# SCH_transmitter.net
KiCad netlist of a schematic drawn in EasyEDA
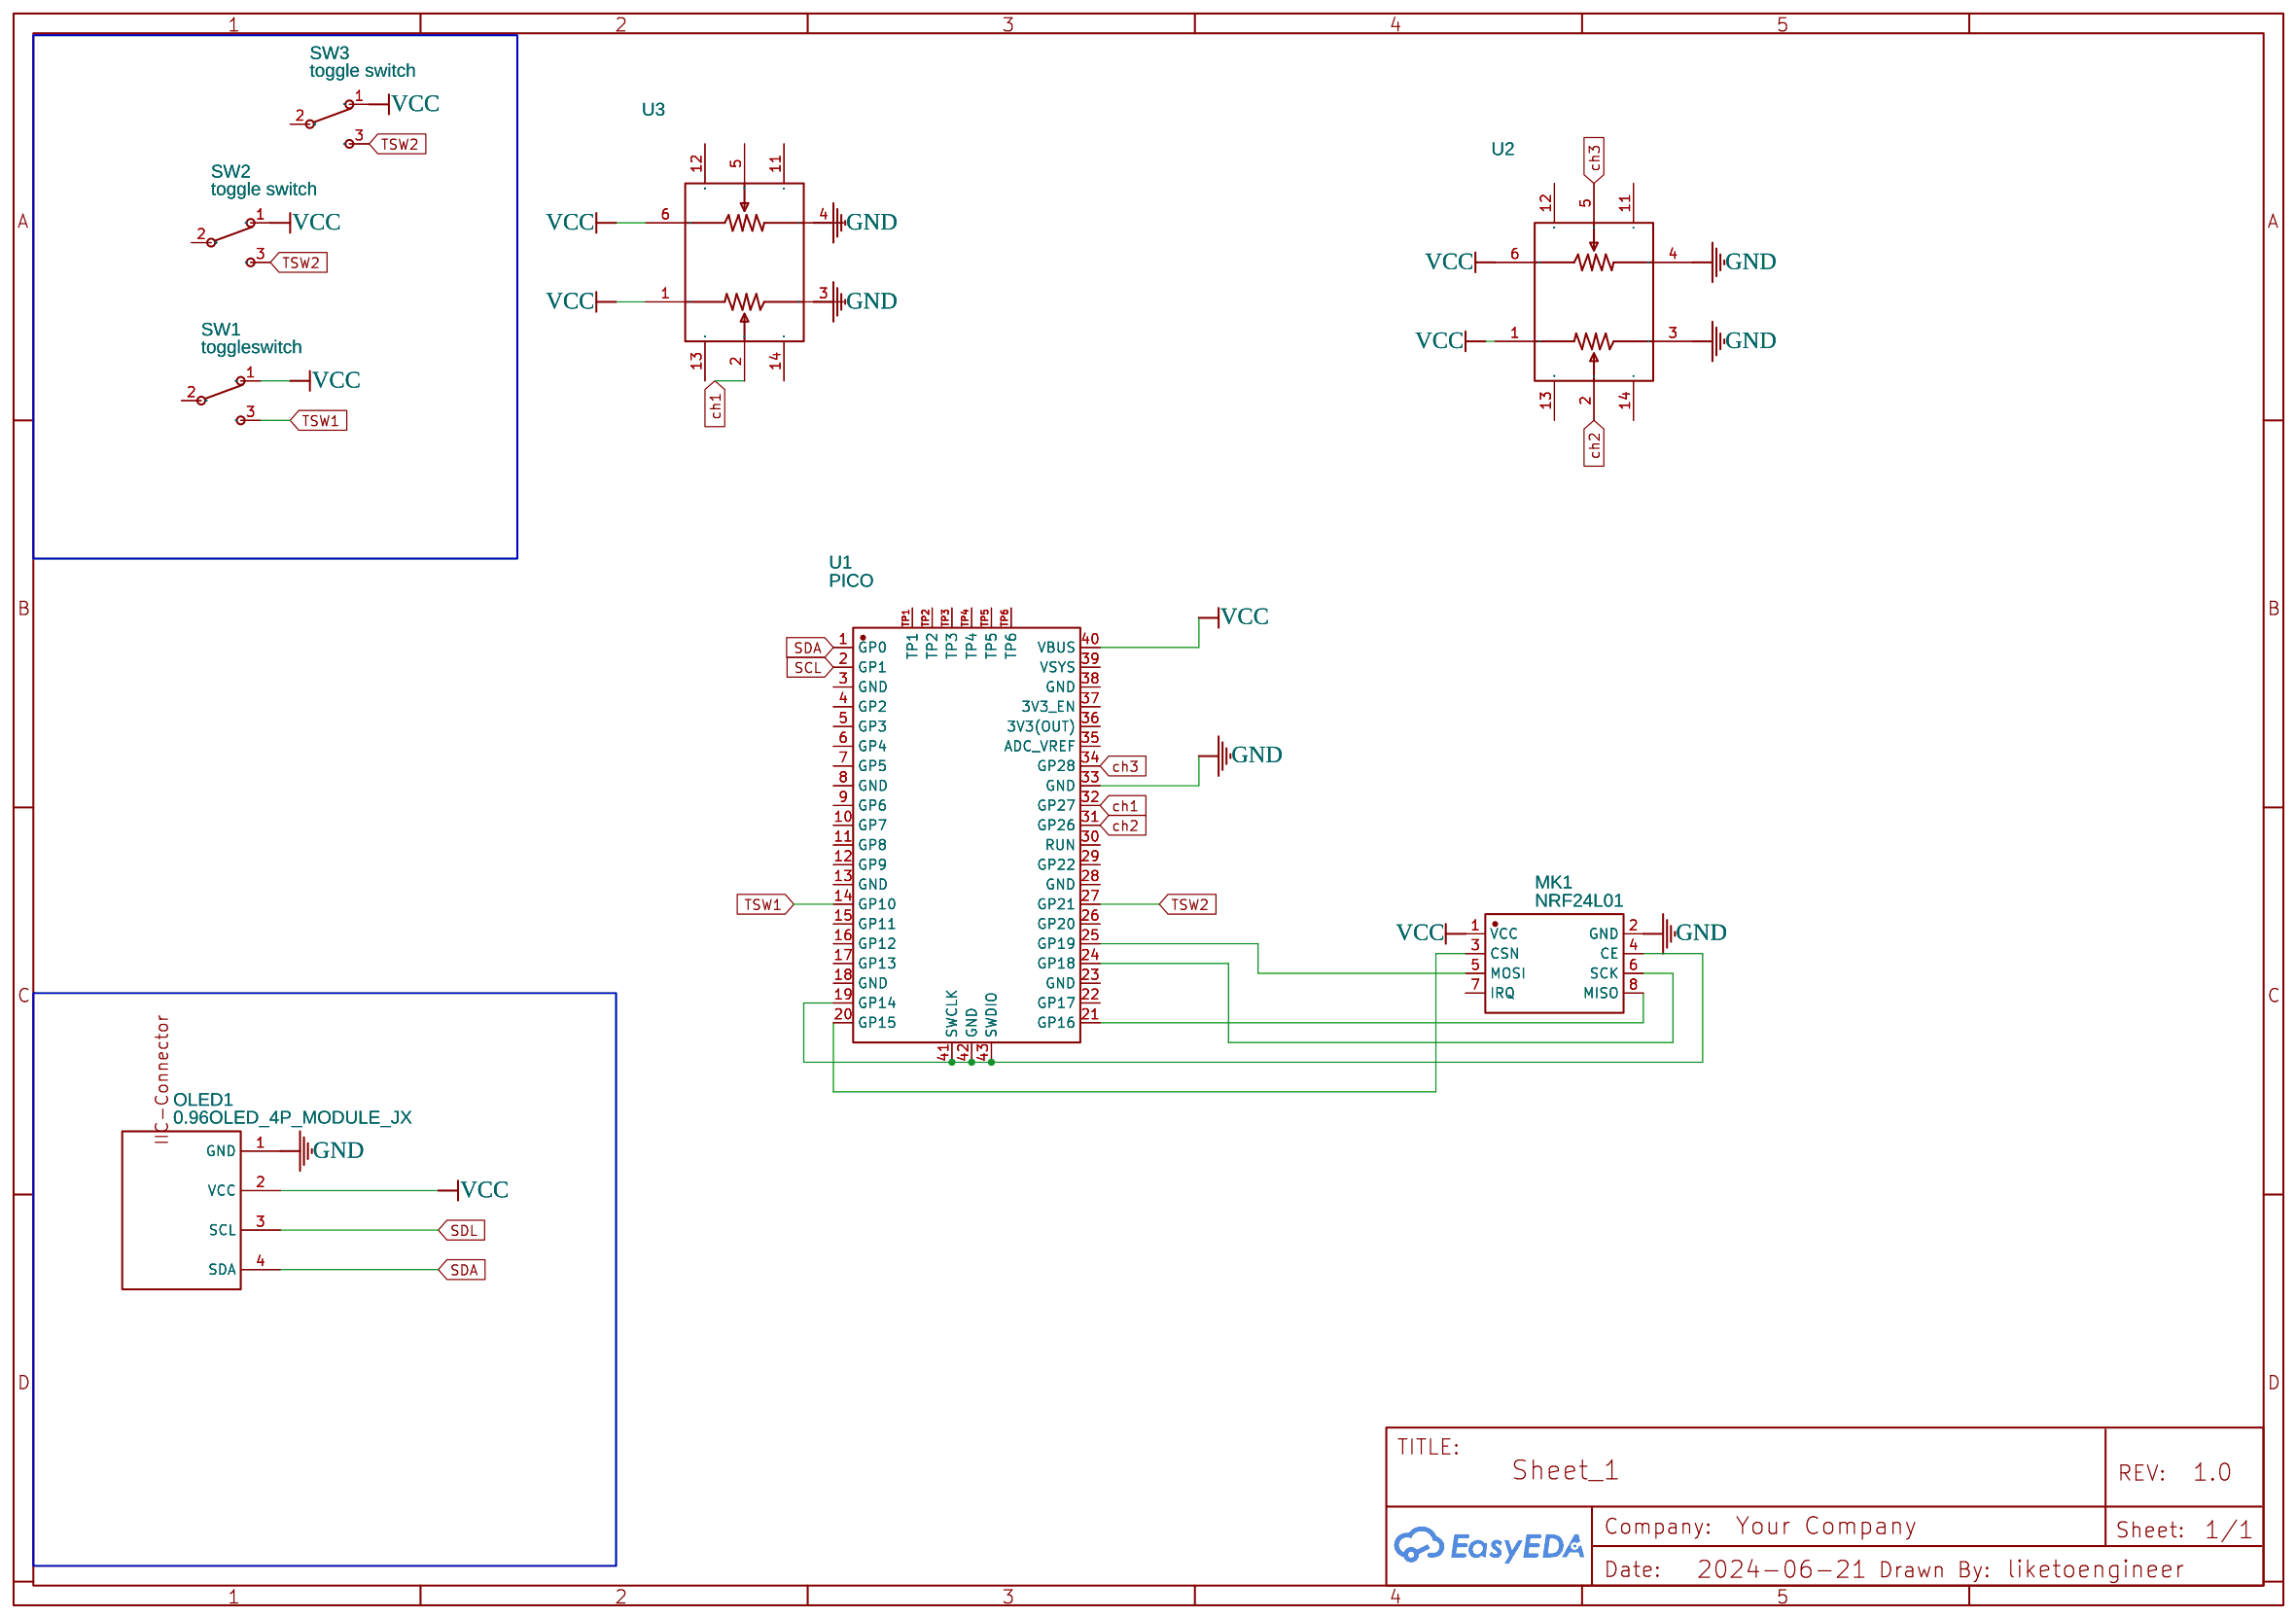
[diagram p0: schematic sheet]

(export (version "E")
  (design (tool "Eeschema 10.0.6"))
  (components
    (comp (ref "MK1")
      (value "NRF24L01")
      (fields (field (name "Manufacturer Part") "NF-04") (field (name "Manufacturer") "Ai-Thinker(安信可)"))
      (libsource (lib "") (part "NRF24L01"))
    )
    (comp (ref "OLED1") (value "0.96OLED_4P_MODULE_JX") (libsource (lib "") (part "0.96OLED_4P_MODULE_JX")))
    (comp (ref "SW1")
      (value "toggleswitch")
      (fields (field (name "Manufacturer Part") "100SP1T2B4M6QE"))
      (libsource (lib "") (part "100SP1T2B4M6QE"))
    )
    (comp (ref "SW2")
      (value "toggle switch")
      (fields (field (name "Manufacturer Part") "100SP1T2B4M6QE"))
      (libsource (lib "") (part "100SP1T2B4M6QE"))
    )
    (comp (ref "SW3")
      (value "toggle switch")
      (fields (field (name "Manufacturer Part") "100SP1T2B4M6QE"))
      (libsource (lib "") (part "100SP1T2B4M6QE"))
    )
    (comp (ref "U1")
      (value "PICO")
      (fields (field (name "Manufacturer") "Raspberry Pi(树莓派)"))
      (libsource (lib "") (part "PICO"))
    )
    (comp (ref "U2")
      (value "252A103B60NA")
      (fields (field (name "Manufacturer") "CTS(西迪斯)"))
      (libsource (lib "") (part "252A103B60NA"))
    )
    (comp (ref "U3")
      (value "252A103B60NA")
      (fields (field (name "Manufacturer") "CTS(西迪斯)"))
      (libsource (lib "") (part "252A103B60NA"))
    )
  )
  (nets
    (net (code "1") (name "GND") (class "Default")
      (node (ref "MK1") (pin "2") (pinfunction "GND_2") (pintype "unspecified"))
      (node (ref "OLED1") (pin "1") (pinfunction "GND_1") (pintype "unspecified"))
      (node (ref "U1") (pin "33") (pinfunction "GND_33") (pintype "unspecified"))
      (node (ref "U2") (pin "3") (pinfunction "3_3") (pintype "unspecified"))
      (node (ref "U2") (pin "4") (pinfunction "4_4") (pintype "unspecified"))
      (node (ref "U3") (pin "3") (pinfunction "3_3") (pintype "unspecified"))
      (node (ref "U3") (pin "4") (pinfunction "4_4") (pintype "unspecified"))
    )
    (net (code "2") (name "Net-(MK1-CE)") (class "Default")
      (node (ref "MK1") (pin "4") (pinfunction "CE_4") (pintype "unspecified"))
      (node (ref "U1") (pin "19") (pinfunction "GP14_19") (pintype "unspecified"))
      (node (ref "U1") (pin "41") (pinfunction "SWCLK_41") (pintype "unspecified"))
      (node (ref "U1") (pin "42") (pinfunction "GND_42") (pintype "unspecified"))
      (node (ref "U1") (pin "43") (pinfunction "SWDIO_43") (pintype "unspecified"))
    )
    (net (code "3") (name "Net-(MK1-CSN)") (class "Default")
      (node (ref "MK1") (pin "3") (pinfunction "CSN_3") (pintype "unspecified"))
      (node (ref "U1") (pin "20") (pinfunction "GP15_20") (pintype "unspecified"))
    )
    (net (code "4") (name "Net-(MK1-MISO)") (class "Default")
      (node (ref "MK1") (pin "8") (pinfunction "MISO_8") (pintype "unspecified"))
      (node (ref "U1") (pin "21") (pinfunction "GP16_21") (pintype "unspecified"))
    )
    (net (code "5") (name "Net-(MK1-MOSI)") (class "Default")
      (node (ref "MK1") (pin "5") (pinfunction "MOSI_5") (pintype "unspecified"))
      (node (ref "U1") (pin "25") (pinfunction "GP19_25") (pintype "unspecified"))
    )
    (net (code "6") (name "Net-(MK1-SCK)") (class "Default")
      (node (ref "MK1") (pin "6") (pinfunction "SCK_6") (pintype "unspecified"))
      (node (ref "U1") (pin "24") (pinfunction "GP18_24") (pintype "unspecified"))
    )
    (net (code "7") (name "SCL") (class "Default")
      (node (ref "U1") (pin "2") (pinfunction "GP1_2") (pintype "unspecified"))
    )
    (net (code "8") (name "SDA") (class "Default")
      (node (ref "OLED1") (pin "4") (pinfunction "SDA_4") (pintype "unspecified"))
      (node (ref "U1") (pin "1") (pinfunction "GP0_1") (pintype "unspecified"))
    )
    (net (code "9") (name "SDL") (class "Default")
      (node (ref "OLED1") (pin "3") (pinfunction "SCL_3") (pintype "unspecified"))
    )
    (net (code "10") (name "TSW1") (class "Default")
      (node (ref "SW1") (pin "3") (pinfunction "NC_3") (pintype "unspecified"))
      (node (ref "U1") (pin "14") (pinfunction "GP10_14") (pintype "unspecified"))
    )
    (net (code "11") (name "TSW2") (class "Default")
      (node (ref "SW2") (pin "3") (pinfunction "NC_3") (pintype "unspecified"))
      (node (ref "SW3") (pin "3") (pinfunction "NC_3") (pintype "unspecified"))
      (node (ref "U1") (pin "27") (pinfunction "GP21_27") (pintype "unspecified"))
    )
    (net (code "12") (name "VCC") (class "Default")
      (node (ref "MK1") (pin "1") (pinfunction "VCC_1") (pintype "unspecified"))
      (node (ref "OLED1") (pin "2") (pinfunction "VCC_2") (pintype "unspecified"))
      (node (ref "SW1") (pin "1") (pinfunction "ON_1") (pintype "unspecified"))
      (node (ref "SW2") (pin "1") (pinfunction "ON_1") (pintype "unspecified"))
      (node (ref "SW3") (pin "1") (pinfunction "ON_1") (pintype "unspecified"))
      (node (ref "U1") (pin "40") (pinfunction "VBUS_40") (pintype "unspecified"))
      (node (ref "U2") (pin "1") (pinfunction "1_1") (pintype "unspecified"))
      (node (ref "U2") (pin "6") (pinfunction "6_6") (pintype "unspecified"))
      (node (ref "U3") (pin "1") (pinfunction "1_1") (pintype "unspecified"))
      (node (ref "U3") (pin "6") (pinfunction "6_6") (pintype "unspecified"))
    )
    (net (code "13") (name "ch1") (class "Default")
      (node (ref "U1") (pin "32") (pinfunction "GP27_32") (pintype "unspecified"))
      (node (ref "U3") (pin "2") (pinfunction "2_2") (pintype "unspecified"))
    )
    (net (code "14") (name "ch2") (class "Default")
      (node (ref "U1") (pin "31") (pinfunction "GP26_31") (pintype "unspecified"))
      (node (ref "U2") (pin "2") (pinfunction "2_2") (pintype "unspecified"))
    )
    (net (code "15") (name "ch3") (class "Default")
      (node (ref "U1") (pin "34") (pinfunction "GP28_34") (pintype "unspecified"))
      (node (ref "U2") (pin "5") (pinfunction "5_5") (pintype "unspecified"))
    )
    (net (code "16") (name "unconnected-(MK1-IRQ-Pad7)") (class "Default")
      (node (ref "MK1") (pin "7") (pinfunction "IRQ_7") (pintype "unspecified"))
    )
    (net (code "17") (name "unconnected-(SW1-COMM-Pad2)") (class "Default")
      (node (ref "SW1") (pin "2") (pinfunction "COMM_2") (pintype "unspecified"))
    )
    (net (code "18") (name "unconnected-(SW2-COMM-Pad2)") (class "Default")
      (node (ref "SW2") (pin "2") (pinfunction "COMM_2") (pintype "unspecified"))
    )
    (net (code "19") (name "unconnected-(SW3-COMM-Pad2)") (class "Default")
      (node (ref "SW3") (pin "2") (pinfunction "COMM_2") (pintype "unspecified"))
    )
    (net (code "20") (name "unconnected-(U1-3V3(OUT)-Pad36)") (class "Default")
      (node (ref "U1") (pin "36") (pinfunction "3V3(OUT)_36") (pintype "unspecified"))
    )
    (net (code "21") (name "unconnected-(U1-3V3_EN-Pad37)") (class "Default")
      (node (ref "U1") (pin "37") (pinfunction "3V3_EN_37") (pintype "unspecified"))
    )
    (net (code "22") (name "unconnected-(U1-ADC_VREF-Pad35)") (class "Default")
      (node (ref "U1") (pin "35") (pinfunction "ADC_VREF_35") (pintype "unspecified"))
    )
    (net (code "23") (name "unconnected-(U1-GND-Pad3)") (class "Default")
      (node (ref "U1") (pin "3") (pinfunction "GND_3") (pintype "unspecified"))
    )
    (net (code "24") (name "unconnected-(U1-GND-Pad8)") (class "Default")
      (node (ref "U1") (pin "8") (pinfunction "GND_8") (pintype "unspecified"))
    )
    (net (code "25") (name "unconnected-(U1-GND-Pad13)") (class "Default")
      (node (ref "U1") (pin "13") (pinfunction "GND_13") (pintype "unspecified"))
    )
    (net (code "26") (name "unconnected-(U1-GND-Pad18)") (class "Default")
      (node (ref "U1") (pin "18") (pinfunction "GND_18") (pintype "unspecified"))
    )
    (net (code "27") (name "unconnected-(U1-GND-Pad23)") (class "Default")
      (node (ref "U1") (pin "23") (pinfunction "GND_23") (pintype "unspecified"))
    )
    (net (code "28") (name "unconnected-(U1-GND-Pad28)") (class "Default")
      (node (ref "U1") (pin "28") (pinfunction "GND_28") (pintype "unspecified"))
    )
    (net (code "29") (name "unconnected-(U1-GND-Pad38)") (class "Default")
      (node (ref "U1") (pin "38") (pinfunction "GND_38") (pintype "unspecified"))
    )
    (net (code "30") (name "unconnected-(U1-GP2-Pad4)") (class "Default")
      (node (ref "U1") (pin "4") (pinfunction "GP2_4") (pintype "unspecified"))
    )
    (net (code "31") (name "unconnected-(U1-GP3-Pad5)") (class "Default")
      (node (ref "U1") (pin "5") (pinfunction "GP3_5") (pintype "unspecified"))
    )
    (net (code "32") (name "unconnected-(U1-GP4-Pad6)") (class "Default")
      (node (ref "U1") (pin "6") (pinfunction "GP4_6") (pintype "unspecified"))
    )
    (net (code "33") (name "unconnected-(U1-GP5-Pad7)") (class "Default")
      (node (ref "U1") (pin "7") (pinfunction "GP5_7") (pintype "unspecified"))
    )
    (net (code "34") (name "unconnected-(U1-GP6-Pad9)") (class "Default")
      (node (ref "U1") (pin "9") (pinfunction "GP6_9") (pintype "unspecified"))
    )
    (net (code "35") (name "unconnected-(U1-GP7-Pad10)") (class "Default")
      (node (ref "U1") (pin "10") (pinfunction "GP7_10") (pintype "unspecified"))
    )
    (net (code "36") (name "unconnected-(U1-GP8-Pad11)") (class "Default")
      (node (ref "U1") (pin "11") (pinfunction "GP8_11") (pintype "unspecified"))
    )
    (net (code "37") (name "unconnected-(U1-GP9-Pad12)") (class "Default")
      (node (ref "U1") (pin "12") (pinfunction "GP9_12") (pintype "unspecified"))
    )
    (net (code "38") (name "unconnected-(U1-GP11-Pad15)") (class "Default")
      (node (ref "U1") (pin "15") (pinfunction "GP11_15") (pintype "unspecified"))
    )
    (net (code "39") (name "unconnected-(U1-GP12-Pad16)") (class "Default")
      (node (ref "U1") (pin "16") (pinfunction "GP12_16") (pintype "unspecified"))
    )
    (net (code "40") (name "unconnected-(U1-GP13-Pad17)") (class "Default")
      (node (ref "U1") (pin "17") (pinfunction "GP13_17") (pintype "unspecified"))
    )
    (net (code "41") (name "unconnected-(U1-GP17-Pad22)") (class "Default")
      (node (ref "U1") (pin "22") (pinfunction "GP17_22") (pintype "unspecified"))
    )
    (net (code "42") (name "unconnected-(U1-GP20-Pad26)") (class "Default")
      (node (ref "U1") (pin "26") (pinfunction "GP20_26") (pintype "unspecified"))
    )
    (net (code "43") (name "unconnected-(U1-GP22-Pad29)") (class "Default")
      (node (ref "U1") (pin "29") (pinfunction "GP22_29") (pintype "unspecified"))
    )
    (net (code "44") (name "unconnected-(U1-PadTP1)") (class "Default")
      (node (ref "U1") (pin "TP1") (pinfunction "TP1_TP1") (pintype "unspecified"))
    )
    (net (code "45") (name "unconnected-(U1-PadTP2)") (class "Default")
      (node (ref "U1") (pin "TP2") (pinfunction "TP2_TP2") (pintype "unspecified"))
    )
    (net (code "46") (name "unconnected-(U1-PadTP3)") (class "Default")
      (node (ref "U1") (pin "TP3") (pinfunction "TP3_TP3") (pintype "unspecified"))
    )
    (net (code "47") (name "unconnected-(U1-PadTP4)") (class "Default")
      (node (ref "U1") (pin "TP4") (pinfunction "TP4_TP4") (pintype "unspecified"))
    )
    (net (code "48") (name "unconnected-(U1-PadTP5)") (class "Default")
      (node (ref "U1") (pin "TP5") (pinfunction "TP5_TP5") (pintype "unspecified"))
    )
    (net (code "49") (name "unconnected-(U1-PadTP6)") (class "Default")
      (node (ref "U1") (pin "TP6") (pinfunction "TP6_TP6") (pintype "unspecified"))
    )
    (net (code "50") (name "unconnected-(U1-RUN-Pad30)") (class "Default")
      (node (ref "U1") (pin "30") (pinfunction "RUN_30") (pintype "unspecified"))
    )
    (net (code "51") (name "unconnected-(U1-VSYS-Pad39)") (class "Default")
      (node (ref "U1") (pin "39") (pinfunction "VSYS_39") (pintype "unspecified"))
    )
    (net (code "52") (name "unconnected-(U2-Pad11)") (class "Default")
      (node (ref "U2") (pin "11") (pinfunction "11_11") (pintype "unspecified"))
    )
    (net (code "53") (name "unconnected-(U2-Pad12)") (class "Default")
      (node (ref "U2") (pin "12") (pinfunction "12_12") (pintype "unspecified"))
    )
    (net (code "54") (name "unconnected-(U2-Pad13)") (class "Default")
      (node (ref "U2") (pin "13") (pinfunction "13_13") (pintype "unspecified"))
    )
    (net (code "55") (name "unconnected-(U2-Pad14)") (class "Default")
      (node (ref "U2") (pin "14") (pinfunction "14_14") (pintype "unspecified"))
    )
    (net (code "56") (name "unconnected-(U3-Pad5)") (class "Default")
      (node (ref "U3") (pin "5") (pinfunction "5_5") (pintype "unspecified"))
    )
    (net (code "57") (name "unconnected-(U3-Pad11)") (class "Default")
      (node (ref "U3") (pin "11") (pinfunction "11_11") (pintype "unspecified"))
    )
    (net (code "58") (name "unconnected-(U3-Pad12)") (class "Default")
      (node (ref "U3") (pin "12") (pinfunction "12_12") (pintype "unspecified"))
    )
    (net (code "59") (name "unconnected-(U3-Pad13)") (class "Default")
      (node (ref "U3") (pin "13") (pinfunction "13_13") (pintype "unspecified"))
    )
    (net (code "60") (name "unconnected-(U3-Pad14)") (class "Default")
      (node (ref "U3") (pin "14") (pinfunction "14_14") (pintype "unspecified"))
    )
  )
)
